# untitled.net
KiCad netlist of a schematic drawn in EAGLE
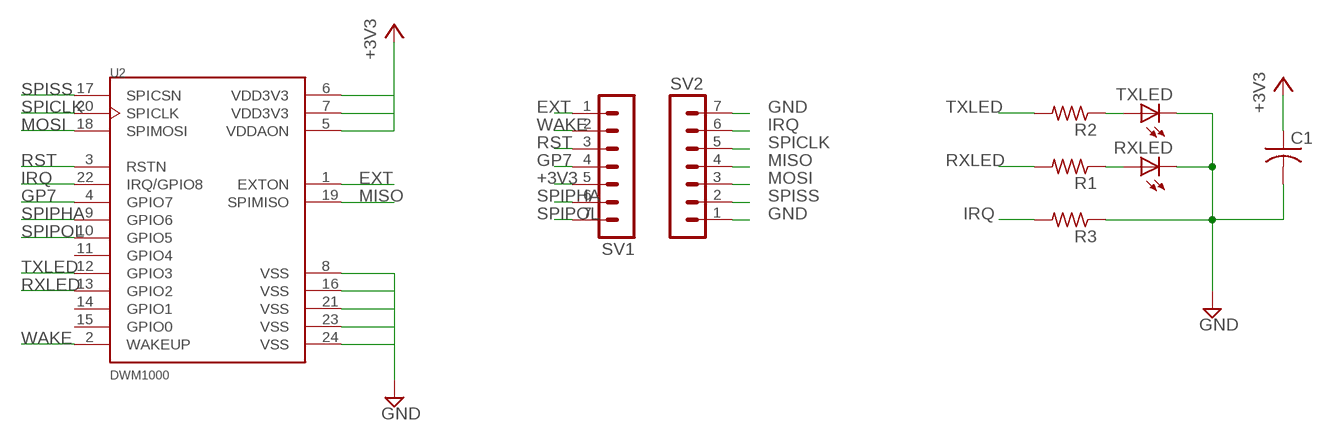
[diagram p0: schematic, sheet 1]

(export (version "E")
  (design (tool "Eeschema 10.0.6"))
  (components
    (comp (ref "C1")
      (value "C-USC1206")
      (footprint "eagle-import:C1206")
      (libsource (lib "eagle-import") (part "C-USC1206"))
    )
    (comp (ref "R1")
      (value "R-US_R1206")
      (footprint "eagle-import:R1206")
      (libsource (lib "eagle-import") (part "R-US_R1206"))
    )
    (comp (ref "R2")
      (value "R-US_R1206")
      (footprint "eagle-import:R1206")
      (libsource (lib "eagle-import") (part "R-US_R1206"))
    )
    (comp (ref "R3")
      (value "R-US_R1206")
      (footprint "eagle-import:R1206")
      (libsource (lib "eagle-import") (part "R-US_R1206"))
    )
    (comp (ref "RXLED")
      (value "LEDSMT1206")
      (footprint "eagle-import:1206")
      (libsource (lib "eagle-import") (part "LEDSMT1206"))
    )
    (comp (ref "SV1")
      (value "MA07-1")
      (footprint "eagle-import:MA07-1")
      (libsource (lib "eagle-import") (part "MA07-1"))
    )
    (comp (ref "SV2")
      (value "MA07-1")
      (footprint "eagle-import:MA07-1")
      (libsource (lib "eagle-import") (part "MA07-1"))
    )
    (comp (ref "TXLED")
      (value "LEDSMT1206")
      (footprint "eagle-import:1206")
      (libsource (lib "eagle-import") (part "LEDSMT1206"))
    )
    (comp (ref "U2")
      (value "DWM1000")
      (footprint "eagle-import:XCVR_DWM1000")
      (fields (field (name "MF") "Decawave"))
      (libsource (lib "eagle-import") (part "DWM1000"))
    )
  )
  (nets
    (net (code "1") (name "+3V3") (class "Default")
      (node (ref "C1") (pin "1") (pinfunction "1_1") (pintype "passive"))
      (node (ref "SV1") (pin "5") (pinfunction "5_5") (pintype "passive"))
      (node (ref "U2") (pin "5") (pinfunction "VDDAON_5") (pintype "power_in"))
      (node (ref "U2") (pin "6") (pinfunction "VDD3V3_6") (pintype "power_in"))
      (node (ref "U2") (pin "7") (pinfunction "VDD3V3_7") (pintype "power_in"))
    )
    (net (code "2") (name "EXT") (class "Default")
      (node (ref "SV1") (pin "1") (pinfunction "1_1") (pintype "passive"))
      (node (ref "U2") (pin "1") (pinfunction "EXTON_1") (pintype "output"))
    )
    (net (code "3") (name "GND") (class "Default")
      (node (ref "C1") (pin "2") (pinfunction "2_2") (pintype "passive"))
      (node (ref "R3") (pin "1") (pinfunction "1_1") (pintype "passive"))
      (node (ref "RXLED") (pin "C") (pinfunction "C_C") (pintype "passive"))
      (node (ref "SV2") (pin "1") (pinfunction "1_1") (pintype "passive"))
      (node (ref "SV2") (pin "7") (pinfunction "7_7") (pintype "passive"))
      (node (ref "TXLED") (pin "C") (pinfunction "C_C") (pintype "passive"))
      (node (ref "U2") (pin "16") (pinfunction "VSS_16") (pintype "power_in"))
      (node (ref "U2") (pin "21") (pinfunction "VSS_21") (pintype "power_in"))
      (node (ref "U2") (pin "23") (pinfunction "VSS_23") (pintype "power_in"))
      (node (ref "U2") (pin "24") (pinfunction "VSS_24") (pintype "power_in"))
      (node (ref "U2") (pin "8") (pinfunction "VSS_8") (pintype "power_in"))
    )
    (net (code "4") (name "GP7") (class "Default")
      (node (ref "SV1") (pin "4") (pinfunction "4_4") (pintype "passive"))
      (node (ref "U2") (pin "4") (pinfunction "GPIO7_4") (pintype "bidirectional"))
    )
    (net (code "5") (name "IRQ") (class "Default")
      (node (ref "R3") (pin "2") (pinfunction "2_2") (pintype "passive"))
      (node (ref "SV2") (pin "6") (pinfunction "6_6") (pintype "passive"))
      (node (ref "U2") (pin "22") (pinfunction "IRQ/GPIO8_22") (pintype "bidirectional"))
    )
    (net (code "6") (name "MISO") (class "Default")
      (node (ref "SV2") (pin "4") (pinfunction "4_4") (pintype "passive"))
      (node (ref "U2") (pin "19") (pinfunction "SPIMISO_19") (pintype "output"))
    )
    (net (code "7") (name "MOSI") (class "Default")
      (node (ref "SV2") (pin "3") (pinfunction "3_3") (pintype "passive"))
      (node (ref "U2") (pin "18") (pinfunction "SPIMOSI_18") (pintype "input"))
    )
    (net (code "8") (name "Net-(R1-Pad1)") (class "Default")
      (node (ref "R1") (pin "1") (pinfunction "1_1") (pintype "passive"))
      (node (ref "RXLED") (pin "A") (pinfunction "A_A") (pintype "passive"))
    )
    (net (code "9") (name "Net-(R2-Pad1)") (class "Default")
      (node (ref "R2") (pin "1") (pinfunction "1_1") (pintype "passive"))
      (node (ref "TXLED") (pin "A") (pinfunction "A_A") (pintype "passive"))
    )
    (net (code "10") (name "RST") (class "Default")
      (node (ref "SV1") (pin "3") (pinfunction "3_3") (pintype "passive"))
      (node (ref "U2") (pin "3") (pinfunction "RSTN_3") (pintype "bidirectional"))
    )
    (net (code "11") (name "RXLED") (class "Default")
      (node (ref "R1") (pin "2") (pinfunction "2_2") (pintype "passive"))
      (node (ref "U2") (pin "13") (pinfunction "GPIO2_13") (pintype "bidirectional"))
    )
    (net (code "12") (name "SPICLK") (class "Default")
      (node (ref "SV2") (pin "5") (pinfunction "5_5") (pintype "passive"))
      (node (ref "U2") (pin "20") (pinfunction "SPICLK_20") (pintype "input"))
    )
    (net (code "13") (name "SPIPHA") (class "Default")
      (node (ref "SV1") (pin "6") (pinfunction "6_6") (pintype "passive"))
      (node (ref "U2") (pin "9") (pinfunction "GPIO6_9") (pintype "bidirectional"))
    )
    (net (code "14") (name "SPIPOL") (class "Default")
      (node (ref "SV1") (pin "7") (pinfunction "7_7") (pintype "passive"))
      (node (ref "U2") (pin "10") (pinfunction "GPIO5_10") (pintype "bidirectional"))
    )
    (net (code "15") (name "SPISS") (class "Default")
      (node (ref "SV2") (pin "2") (pinfunction "2_2") (pintype "passive"))
      (node (ref "U2") (pin "17") (pinfunction "SPICSN_17") (pintype "input"))
    )
    (net (code "16") (name "TXLED") (class "Default")
      (node (ref "R2") (pin "2") (pinfunction "2_2") (pintype "passive"))
      (node (ref "U2") (pin "12") (pinfunction "GPIO3_12") (pintype "bidirectional"))
    )
    (net (code "17") (name "WAKE") (class "Default")
      (node (ref "SV1") (pin "2") (pinfunction "2_2") (pintype "passive"))
      (node (ref "U2") (pin "2") (pinfunction "WAKEUP_2") (pintype "bidirectional"))
    )
    (net (code "18") (name "unconnected-(U2-GPIO0-Pad15)") (class "Default")
      (node (ref "U2") (pin "15") (pinfunction "GPIO0_15") (pintype "bidirectional"))
    )
    (net (code "19") (name "unconnected-(U2-GPIO1-Pad14)") (class "Default")
      (node (ref "U2") (pin "14") (pinfunction "GPIO1_14") (pintype "bidirectional"))
    )
    (net (code "20") (name "unconnected-(U2-GPIO4-Pad11)") (class "Default")
      (node (ref "U2") (pin "11") (pinfunction "GPIO4_11") (pintype "bidirectional"))
    )
  )
)
